# esquetematico_PWM.net
KiCad netlist of a schematic drawn in Altium Designer
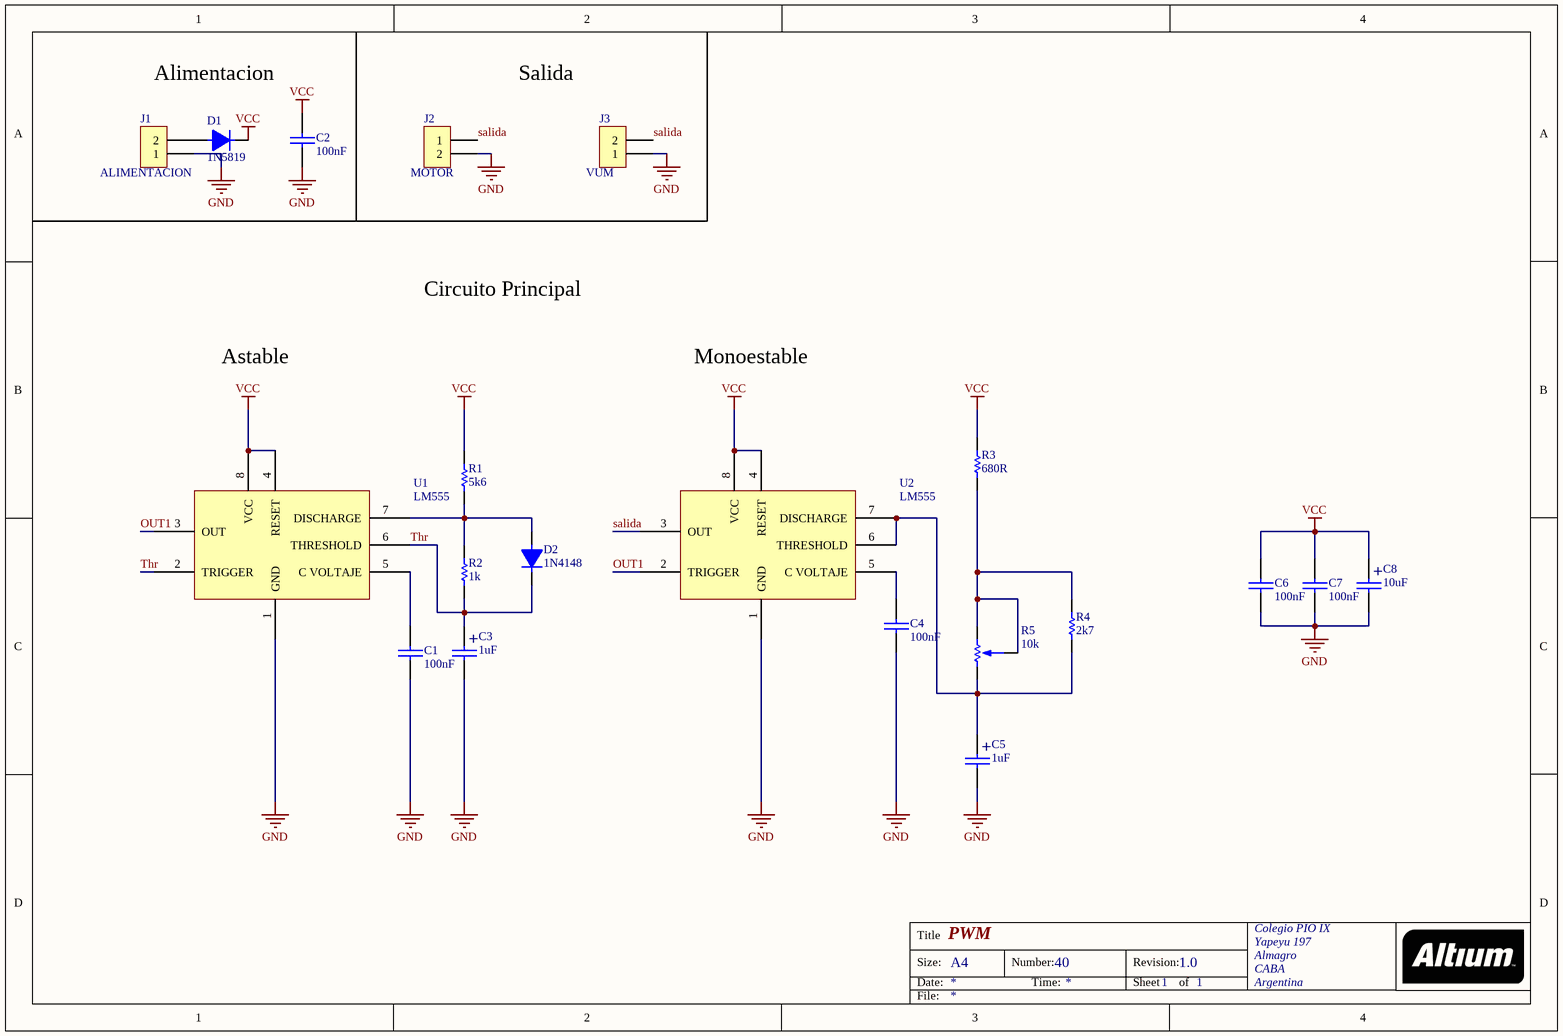
[diagram p0: esquetematico PWM.SchDoc]

(export (version "E")
  (design (tool "Eeschema 10.0.6"))
  (components
    (comp (ref "C1") (value "100nF") (footprint "CAP100") (libsource (lib "Libreria4") (part "CAP")))
    (comp (ref "C2") (value "100nF") (footprint "CAP100") (libsource (lib "Libreria4") (part "CAP")))
    (comp (ref "C3") (value "1uF") (footprint "CAP100RP") (libsource (lib "LIBPIOIX 0314A") (part "CAPPOL")))
    (comp (ref "C4") (value "100nF") (footprint "CAP100") (libsource (lib "Libreria4") (part "CAP")))
    (comp (ref "C5") (value "1uF") (footprint "CAP100RP") (libsource (lib "LIBPIOIX 0314A") (part "CAPPOL")))
    (comp (ref "C6") (value "100nF") (footprint "CAP200") (libsource (lib "LIBEBAL") (part "CAP")))
    (comp (ref "C7") (value "100nF") (footprint "CAP200") (libsource (lib "LIBEBAL") (part "CAP")))
    (comp (ref "C8") (value "10uF") (footprint "CAP100RP") (libsource (lib "LIBPIOIX 0314A") (part "CAPPOL")))
    (comp (ref "D1") (value "1N5819") (footprint "DO41") (libsource (lib "LIBPIOIX 0314A") (part "DIODO")))
    (comp (ref "D2") (value "1N4148") (footprint "DO41") (libsource (lib "LIBPIOIX 0314A") (part "DIODO")))
    (comp (ref "J1")
      (value "ALIMENTACION")
      (footprint "BORNERA2")
      (libsource (lib "Schematics") (part "BORNERA 2"))
    )
    (comp (ref "J2") (value "MOTOR") (footprint "BORNERA2") (libsource (lib "") (part "BORNERA 2_1")))
    (comp (ref "J3") (value "VUM") (footprint "BORNERA2") (libsource (lib "Schematics") (part "BORNERA 2")))
    (comp (ref "R1") (value "5k6") (footprint "RES400") (libsource (lib "LIBPIOIX 0314A") (part "RES")))
    (comp (ref "R2") (value "1k") (footprint "RES400") (libsource (lib "LIBPIOIX 0314A") (part "RES")))
    (comp (ref "R3") (value "680R") (footprint "RES400") (libsource (lib "LIBPIOIX 0314A") (part "RES")))
    (comp (ref "R4") (value "2k7") (footprint "RES400") (libsource (lib "LIBPIOIX 0314A") (part "RES")))
    (comp (ref "R5") (value "10k") (footprint "PRESET V") (libsource (lib "LIBPIOIX 0314A") (part "PRESET")))
    (comp (ref "U1")
      (value "LM555")
      (footprint "DIP8")
      (description "Timer")
      (libsource (lib "Libreria4") (part "LM555"))
    )
    (comp (ref "U2")
      (value "LM555")
      (footprint "DIP8")
      (description "Timer")
      (libsource (lib "Libreria4") (part "LM555"))
    )
  )
  (nets
    (net (code "1") (name "/OUT1") (class "Default")
      (node (ref "U1") (pin "3") (pinfunction "OUT_3") (pintype "passive"))
      (node (ref "U2") (pin "2") (pinfunction "TRIGGER_2") (pintype "passive"))
    )
    (net (code "2") (name "/Thr") (class "Default")
      (node (ref "C3") (pin "1") (pinfunction "1_1") (pintype "passive"))
      (node (ref "D2") (pin "2") (pinfunction "2_2") (pintype "passive"))
      (node (ref "R2") (pin "1") (pinfunction "1_1") (pintype "passive"))
      (node (ref "U1") (pin "2") (pinfunction "TRIGGER_2") (pintype "passive"))
      (node (ref "U1") (pin "6") (pinfunction "THRESHOLD_6") (pintype "passive"))
    )
    (net (code "3") (name "/salida") (class "Default")
      (node (ref "J2") (pin "1") (pinfunction "1_1") (pintype "passive"))
      (node (ref "J3") (pin "2") (pinfunction "2_2") (pintype "passive"))
      (node (ref "U2") (pin "3") (pinfunction "OUT_3") (pintype "passive"))
    )
    (net (code "4") (name "GND") (class "Default")
      (node (ref "C1") (pin "2") (pinfunction "2_2") (pintype "passive"))
      (node (ref "C2") (pin "2") (pinfunction "2_2") (pintype "passive"))
      (node (ref "C3") (pin "2") (pinfunction "2_2") (pintype "passive"))
      (node (ref "C4") (pin "2") (pinfunction "2_2") (pintype "passive"))
      (node (ref "C5") (pin "2") (pinfunction "2_2") (pintype "passive"))
      (node (ref "C6") (pin "2") (pinfunction "2_2") (pintype "passive"))
      (node (ref "C7") (pin "2") (pinfunction "2_2") (pintype "passive"))
      (node (ref "C8") (pin "2") (pinfunction "2_2") (pintype "passive"))
      (node (ref "J1") (pin "1") (pinfunction "1_1") (pintype "passive"))
      (node (ref "J2") (pin "2") (pinfunction "2_2") (pintype "passive"))
      (node (ref "J3") (pin "1") (pinfunction "1_1") (pintype "passive"))
      (node (ref "U1") (pin "1") (pinfunction "GND_1") (pintype "passive"))
      (node (ref "U2") (pin "1") (pinfunction "GND_1") (pintype "passive"))
    )
    (net (code "5") (name "Net-(D1-Pad1)") (class "Default")
      (node (ref "D1") (pin "1") (pinfunction "1_1") (pintype "passive"))
      (node (ref "J1") (pin "2") (pinfunction "2_2") (pintype "passive"))
    )
    (net (code "6") (name "Net-(R3-Pad1)") (class "Default")
      (node (ref "R3") (pin "1") (pinfunction "1_1") (pintype "passive"))
      (node (ref "R4") (pin "2") (pinfunction "2_2") (pintype "passive"))
      (node (ref "R5") (pin "1") (pinfunction "1_1") (pintype "passive"))
      (node (ref "R5") (pin "2") (pinfunction "2_2") (pintype "passive"))
    )
    (net (code "7") (name "Net-(U1-C_VOLTAJE)") (class "Default")
      (node (ref "C1") (pin "1") (pinfunction "1_1") (pintype "passive"))
      (node (ref "U1") (pin "5") (pinfunction "C_VOLTAJE_5") (pintype "passive"))
    )
    (net (code "8") (name "Net-(U1-DISCHARGE)") (class "Default")
      (node (ref "D2") (pin "1") (pinfunction "1_1") (pintype "passive"))
      (node (ref "R1") (pin "1") (pinfunction "1_1") (pintype "passive"))
      (node (ref "R2") (pin "2") (pinfunction "2_2") (pintype "passive"))
      (node (ref "U1") (pin "7") (pinfunction "DISCHARGE_7") (pintype "passive"))
    )
    (net (code "9") (name "Net-(U2-C_VOLTAJE)") (class "Default")
      (node (ref "C4") (pin "1") (pinfunction "1_1") (pintype "passive"))
      (node (ref "U2") (pin "5") (pinfunction "C_VOLTAJE_5") (pintype "passive"))
    )
    (net (code "10") (name "Net-(U2-DISCHARGE)") (class "Default")
      (node (ref "C5") (pin "1") (pinfunction "1_1") (pintype "passive"))
      (node (ref "R4") (pin "1") (pinfunction "1_1") (pintype "passive"))
      (node (ref "R5") (pin "3") (pinfunction "3_3") (pintype "passive"))
      (node (ref "U2") (pin "6") (pinfunction "THRESHOLD_6") (pintype "passive"))
      (node (ref "U2") (pin "7") (pinfunction "DISCHARGE_7") (pintype "passive"))
    )
    (net (code "11") (name "VCC") (class "Default")
      (node (ref "C2") (pin "1") (pinfunction "1_1") (pintype "passive"))
      (node (ref "C6") (pin "1") (pinfunction "1_1") (pintype "passive"))
      (node (ref "C7") (pin "1") (pinfunction "1_1") (pintype "passive"))
      (node (ref "C8") (pin "1") (pinfunction "1_1") (pintype "passive"))
      (node (ref "D1") (pin "2") (pinfunction "2_2") (pintype "passive"))
      (node (ref "R1") (pin "2") (pinfunction "2_2") (pintype "passive"))
      (node (ref "R3") (pin "2") (pinfunction "2_2") (pintype "passive"))
      (node (ref "U1") (pin "4") (pinfunction "RESET_4") (pintype "passive"))
      (node (ref "U1") (pin "8") (pinfunction "VCC_8") (pintype "passive"))
      (node (ref "U2") (pin "4") (pinfunction "RESET_4") (pintype "passive"))
      (node (ref "U2") (pin "8") (pinfunction "VCC_8") (pintype "passive"))
    )
  )
)
